# 3020_0323.net
KiCad netlist of a schematic drawn in EasyEDA Pro
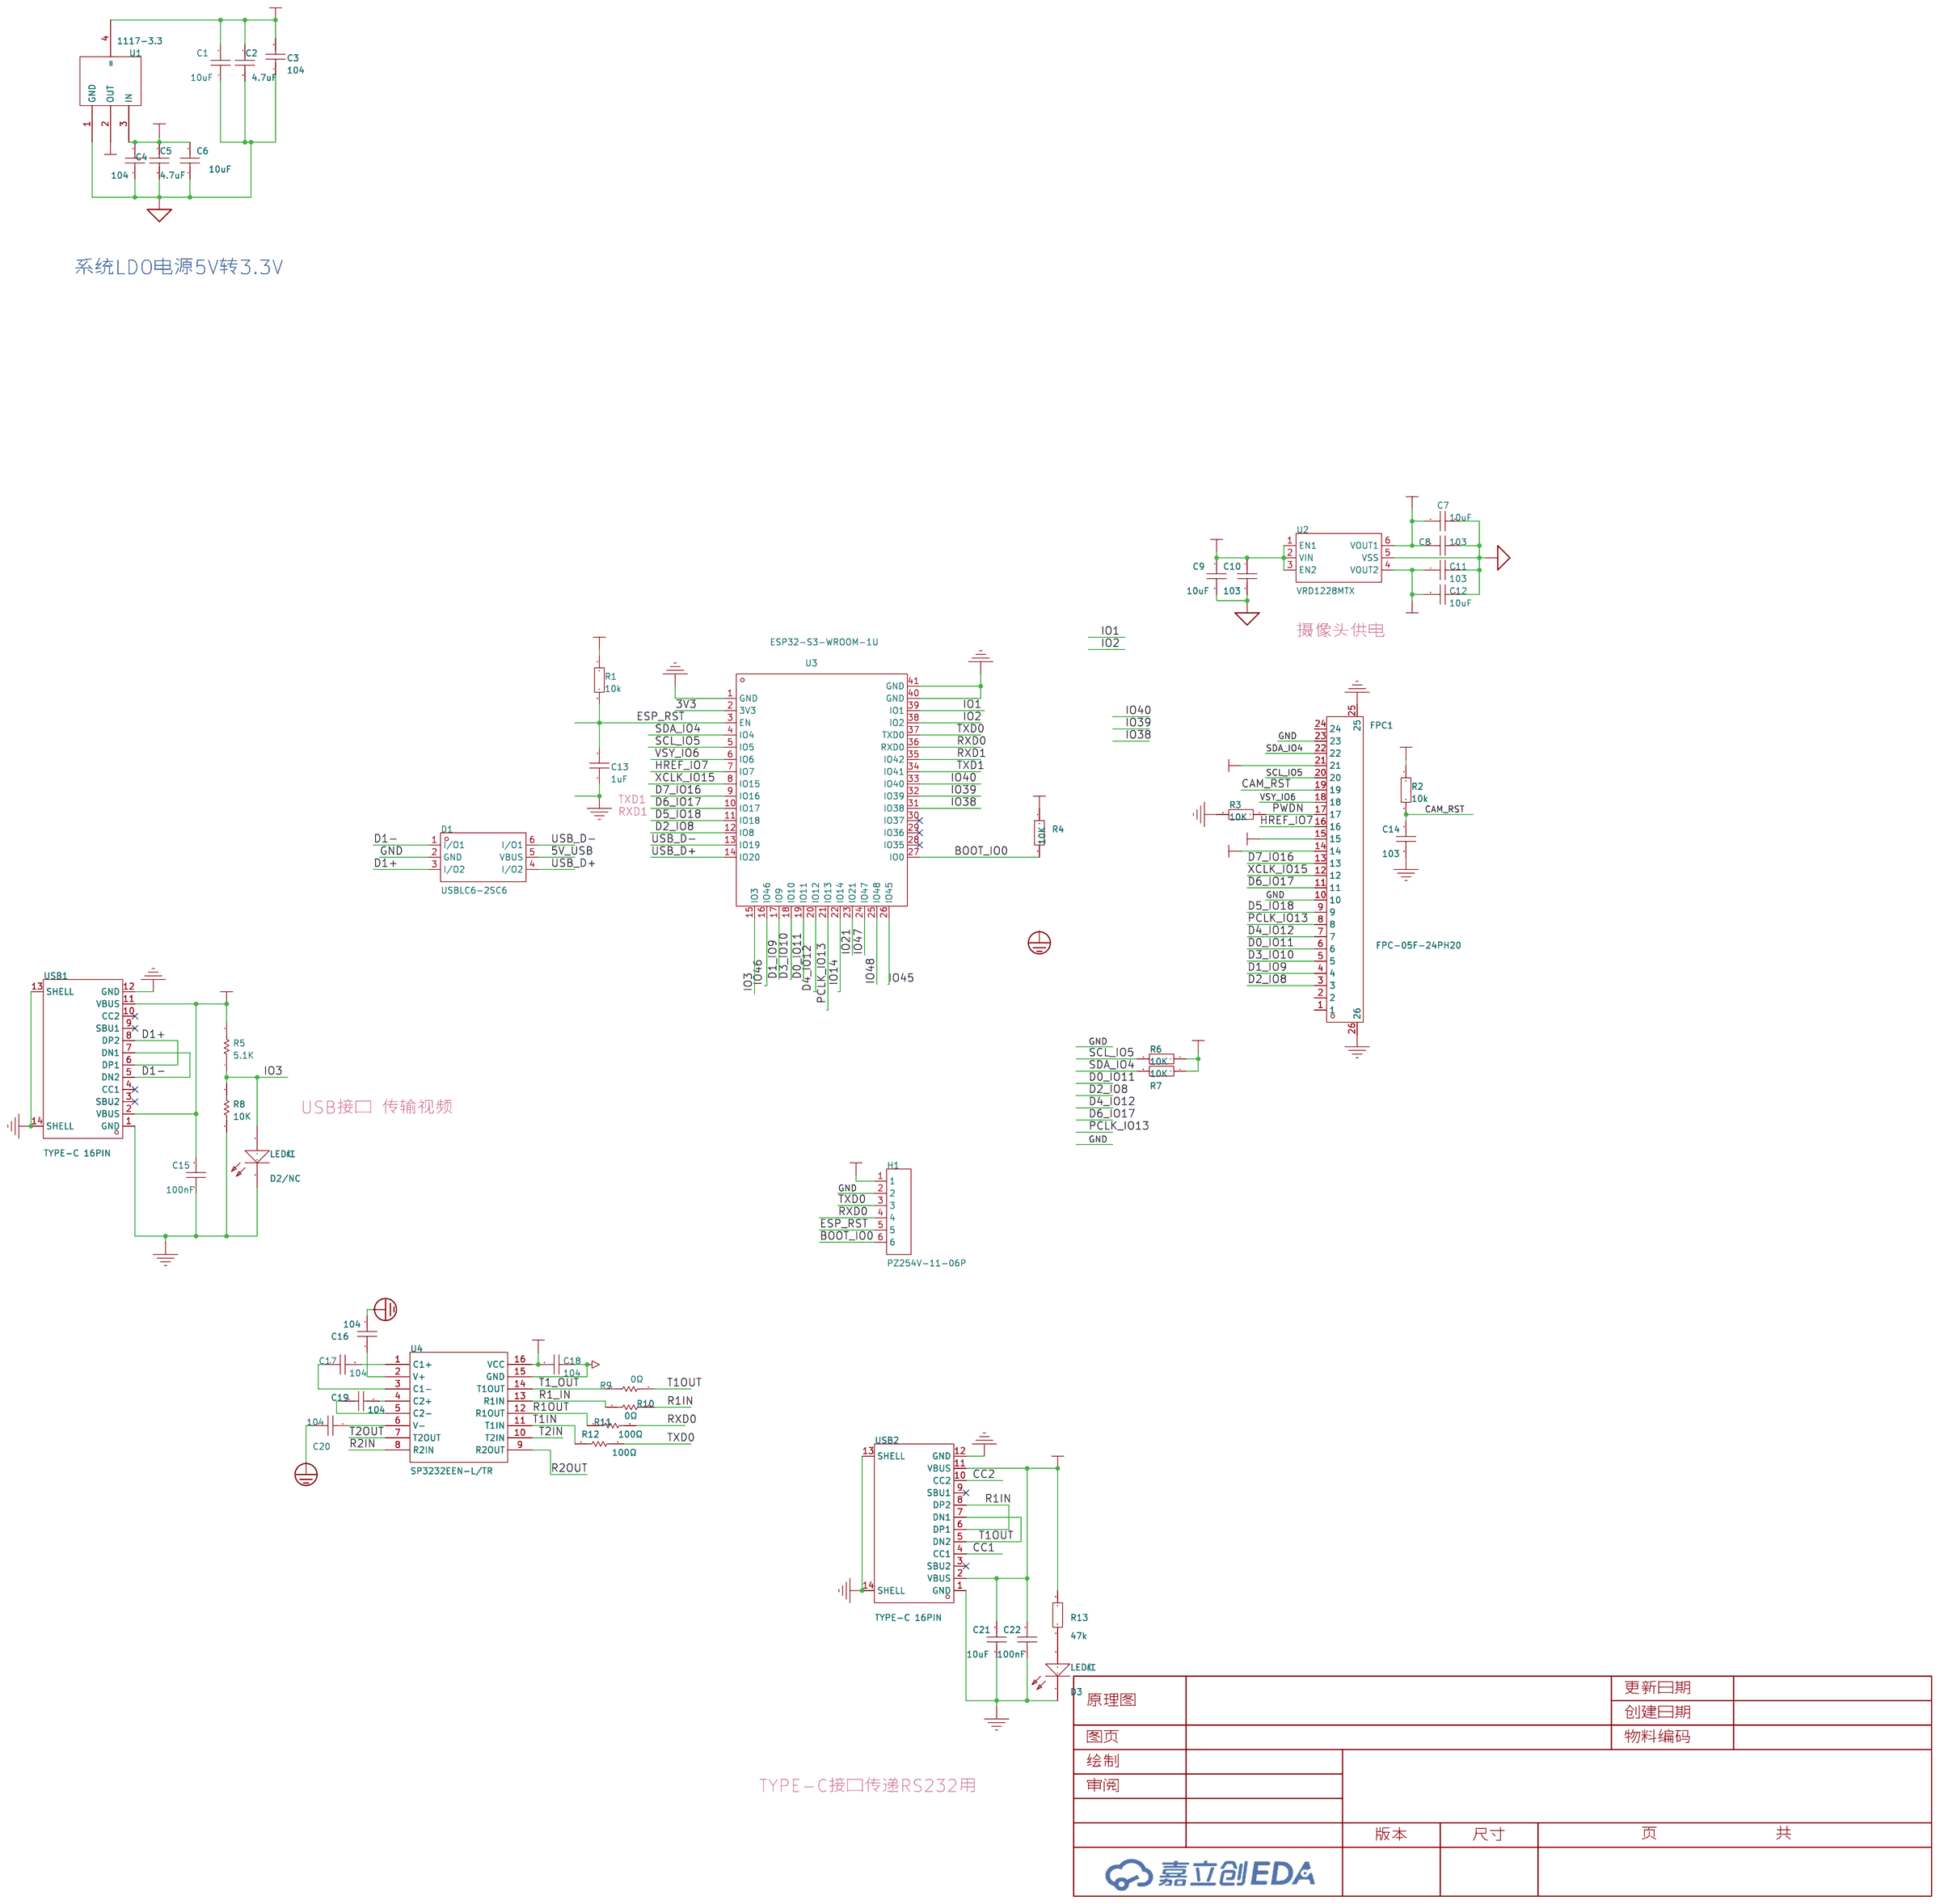
[diagram p0: schematic sheet]

(export (version "E")
  (design (tool "Eeschema 10.0.6"))
  (components
    (comp (ref "C1") (value "10uF") (libsource (lib "easyedapro") (part "CAP")))
    (comp (ref "C2") (value "4.7uF") (libsource (lib "easyedapro") (part "CAP")))
    (comp (ref "C3")
      (value "104")
      (footprint "easyedapro:0603C")
      (description "Capacitor (Semiconductor SIM Model)")
      (libsource (lib "easyedapro") (part "Cap Semi"))
    )
    (comp (ref "C4")
      (value "104")
      (footprint "easyedapro:0603C")
      (description "Capacitor (Semiconductor SIM Model)")
      (libsource (lib "easyedapro") (part "Cap Semi"))
    )
    (comp (ref "C5") (value "4.7uF") (libsource (lib "easyedapro") (part "CAP")))
    (comp (ref "C6") (value "10uF") (libsource (lib "easyedapro") (part "CAP")))
    (comp (ref "C7") (value "10uF") (libsource (lib "easyedapro") (part "CAP")))
    (comp (ref "C8")
      (value "18pF")
      (footprint "easyedapro:0603C")
      (description "Capacitor (Semiconductor SIM Model)")
      (libsource (lib "easyedapro") (part "Cap Semi"))
    )
    (comp (ref "C9") (value "10uF") (libsource (lib "easyedapro") (part "CAP")))
    (comp (ref "C10")
      (value "18pF")
      (footprint "easyedapro:0603C")
      (description "Capacitor (Semiconductor SIM Model)")
      (libsource (lib "easyedapro") (part "Cap Semi"))
    )
    (comp (ref "C11")
      (value "18pF")
      (footprint "easyedapro:0603C")
      (description "Capacitor (Semiconductor SIM Model)")
      (libsource (lib "easyedapro") (part "Cap Semi"))
    )
    (comp (ref "C12") (value "10uF") (libsource (lib "easyedapro") (part "CAP")))
    (comp (ref "C13")
      (value "1uF")
      (footprint "easyedapro:C0603")
      (description "Capacitor")
      (libsource (lib "easyedapro") (part "Cap"))
    )
    (comp (ref "C14")
      (value "18pF")
      (footprint "easyedapro:0603C")
      (description "Capacitor (Semiconductor SIM Model)")
      (libsource (lib "easyedapro") (part "Cap Semi"))
    )
    (comp (ref "C15")
      (value "100nF")
      (footprint "easyedapro:C0603")
      (description "Capacitor")
      (libsource (lib "easyedapro") (part "Cap"))
    )
    (comp (ref "C16")
      (value "104")
      (footprint "easyedapro:0603C")
      (description "Capacitor (Semiconductor SIM Model)")
      (libsource (lib "easyedapro") (part "Cap Semi"))
    )
    (comp (ref "C17")
      (value "104")
      (footprint "easyedapro:0603C")
      (description "Capacitor (Semiconductor SIM Model)")
      (libsource (lib "easyedapro") (part "Cap Semi"))
    )
    (comp (ref "C18")
      (value "104")
      (footprint "easyedapro:0603C")
      (description "Capacitor (Semiconductor SIM Model)")
      (libsource (lib "easyedapro") (part "Cap Semi"))
    )
    (comp (ref "C19")
      (value "104")
      (footprint "easyedapro:0603C")
      (description "Capacitor (Semiconductor SIM Model)")
      (libsource (lib "easyedapro") (part "Cap Semi"))
    )
    (comp (ref "C20")
      (value "104")
      (footprint "easyedapro:0603C")
      (description "Capacitor (Semiconductor SIM Model)")
      (libsource (lib "easyedapro") (part "Cap Semi"))
    )
    (comp (ref "C21") (value "10uF") (libsource (lib "easyedapro") (part "CAP")))
    (comp (ref "C22")
      (value "100nF")
      (footprint "easyedapro:C0603")
      (description "Capacitor")
      (libsource (lib "easyedapro") (part "Cap"))
    )
    (comp (ref "D1")
      (value "USBLC6-2SC6")
      (footprint "easyedapro:SOT-23-6_L2.9-W1.6-P0.95-LS2.8-BL")
      (description "最大钳位电压:15V;击穿电压:6V;")
      (fields (field (name "Manufacturer") "UMW(友台半导体)"))
      (libsource (lib "easyedapro") (part "USBLC6-2SC6_C2687116"))
    )
    (comp (ref "D2/NC")
      (value "LED红")
      (footprint "easyedapro:0603L")
      (description "Typical BLUE SiC LED")
      (libsource (lib "easyedapro") (part "LED3"))
    )
    (comp (ref "D3")
      (value "LED红")
      (footprint "easyedapro:0603L")
      (description "Typical BLUE SiC LED")
      (libsource (lib "easyedapro") (part "LED3"))
    )
    (comp (ref "FPC1")
      (value "FPC-05F-24PH20")
      (footprint "easyedapro:FPC-SMD_24P-P0.50_FPC-05F-24PH20")
      (description "锁定特性:翻盖式;触点类型:卧贴;触点数量:24P;间距:0.5mm;安装方式:下接;工作温度:-25°C~+85°C;")
      (fields (field (name "Manufacturer") "XUNPU(讯普)"))
      (libsource (lib "easyedapro") (part "FPC-05F-24PH20"))
    )
    (comp (ref "H1")
      (value "PZ254V-11-06P")
      (footprint "easyedapro:HDR-TH_6P-P2.54-V-M")
      (fields (field (name "Manufacturer") "XFCN(兴飞)"))
      (libsource (lib "easyedapro") (part "PZ254V-11-06P"))
    )
    (comp (ref "R1")
      (value "10k")
      (footprint "easyedapro:R0603")
      (description "电阻类型:薄膜电阻;阻值:10kΩ;精度:±0.1%;功率:100mW;温度系数:±25ppm/;最大工作电压:75V;工作温度范围:-55~+155;")
      (fields
        (field (name "Manufacturer Part") "RT0603BRD0710KL")
        (field (name "Manufacturer") "YAGEO(----)")
      )
      (libsource (lib "easyedapro") (part "RT0603BRD0710KL"))
    )
    (comp (ref "R2")
      (value "10k")
      (footprint "easyedapro:R0603")
      (description "电阻类型:薄膜电阻;阻值:10kΩ;精度:±0.1%;功率:100mW;温度系数:±25ppm/;最大工作电压:75V;工作温度范围:-55~+155;")
      (fields
        (field (name "Manufacturer Part") "RT0603BRD0710KL")
        (field (name "Manufacturer") "YAGEO(----)")
      )
      (libsource (lib "easyedapro") (part "RT0603BRD0710KL"))
    )
    (comp (ref "R3")
      (value "10K")
      (footprint "easyedapro:R0603")
      (description "电阻类型:薄膜电阻;阻值:10kΩ;精度:±0.1%;功率:100mW;温度系数:±25ppm/;最大工作电压:75V;工作温度范围:-55~+155;")
      (fields
        (field (name "Manufacturer Part") "RT0603BRD0710KL")
        (field (name "Manufacturer") "YAGEO(----)")
      )
      (libsource (lib "easyedapro") (part "RT0603BRD0710KL"))
    )
    (comp (ref "R4")
      (value "10K")
      (footprint "easyedapro:R0603")
      (description "电阻类型:薄膜电阻;阻值:10kΩ;精度:±0.1%;功率:100mW;温度系数:±25ppm/;最大工作电压:75V;工作温度范围:-55~+155;")
      (fields
        (field (name "Manufacturer Part") "RT0603BRD0710KL")
        (field (name "Manufacturer") "YAGEO(----)")
      )
      (libsource (lib "easyedapro") (part "RT0603BRD0710KL"))
    )
    (comp (ref "R5")
      (value "10K")
      (footprint "easyedapro:0603R")
      (description "Resistor")
      (libsource (lib "easyedapro") (part "RES"))
    )
    (comp (ref "R6")
      (value "10K")
      (footprint "easyedapro:R0603")
      (description "电阻类型:薄膜电阻;阻值:10kΩ;精度:±0.1%;功率:100mW;温度系数:±25ppm/;最大工作电压:75V;工作温度范围:-55~+155;")
      (fields
        (field (name "Manufacturer Part") "RT0603BRD0710KL")
        (field (name "Manufacturer") "YAGEO(----)")
      )
      (libsource (lib "easyedapro") (part "RT0603BRD0710KL"))
    )
    (comp (ref "R7")
      (value "10K")
      (footprint "easyedapro:R0603")
      (description "电阻类型:薄膜电阻;阻值:10kΩ;精度:±0.1%;功率:100mW;温度系数:±25ppm/;最大工作电压:75V;工作温度范围:-55~+155;")
      (fields
        (field (name "Manufacturer Part") "RT0603BRD0710KL")
        (field (name "Manufacturer") "YAGEO(----)")
      )
      (libsource (lib "easyedapro") (part "RT0603BRD0710KL"))
    )
    (comp (ref "R8")
      (value "10K")
      (footprint "easyedapro:0603R")
      (description "Resistor")
      (libsource (lib "easyedapro") (part "RES"))
    )
    (comp (ref "R9")
      (value "0Ω")
      (footprint "easyedapro:0603R")
      (description "Resistor")
      (libsource (lib "easyedapro") (part "RES"))
    )
    (comp (ref "R10")
      (value "0Ω")
      (footprint "easyedapro:0603R")
      (description "Resistor")
      (libsource (lib "easyedapro") (part "RES"))
    )
    (comp (ref "R11")
      (value "100Ω")
      (footprint "easyedapro:0603R")
      (description "Resistor")
      (libsource (lib "easyedapro") (part "RES"))
    )
    (comp (ref "R12")
      (value "100Ω")
      (footprint "easyedapro:0603R")
      (description "Resistor")
      (libsource (lib "easyedapro") (part "RES"))
    )
    (comp (ref "R13")
      (value "47k")
      (footprint "easyedapro:R0603")
      (description "电阻类型:薄膜电阻;阻值:10kΩ;精度:±0.1%;功率:100mW;温度系数:±25ppm/;最大工作电压:75V;工作温度范围:-55~+155;")
      (fields
        (field (name "Manufacturer Part") "RT0603BRD0710KL")
        (field (name "Manufacturer") "YAGEO(----)")
      )
      (libsource (lib "easyedapro") (part "RT0603BRD0710KL"))
    )
    (comp (ref "U1")
      (value "1117-3.3")
      (footprint "easyedapro:SOT-223")
      (libsource (lib "easyedapro") (part "LM1117"))
    )
    (comp (ref "U2")
      (value "VRD1228MTX")
      (footprint "easyedapro:SOT-23-6_L2.9-W1.6-P0.95-LS2.8-BL")
      (description "输出类型:-;工作电压:6V;输出电压:1.2V；2.8V;输出电流:-;电源纹波抑制比(PSRR):75dB@(1kHz);输出极性:正极;")
      (fields (field (name "Manufacturer") "AnaSem(安纳森)"))
      (libsource (lib "easyedapro") (part "VRD1228MTX"))
    )
    (comp (ref "U3")
      (value "ESP32-S3-WROOM-1U")
      (footprint "easyedapro:ESP32-S3-WROOM-1U")
      (fields
        (field (name "Manufacturer Part") "ESP32-S3-WROOM-1(N16R2)")
        (field (name "Manufacturer") "ESPRESSIF(----)")
      )
      (libsource (lib "easyedapro") (part "ESP32-S3-WROOM-1(N16R2)"))
    )
    (comp (ref "U4")
      (value "SP3232EEN-L/TR")
      (footprint "easyedapro:SOIC-16_L9.9-W3.9-P1.27-LS6.0-BL")
      (description "类型:收发器;数据速率:235Kbps;")
      (fields (field (name "Manufacturer") "MaxLinear(迈凌)"))
      (libsource (lib "easyedapro") (part "SP3232EEN-L/TR"))
    )
    (comp (ref "USB1")
      (value "TYPE-C 16PIN")
      (footprint "easyedapro:USB-C-SMD_TYPE-C-6PIN-2MD-073")
      (description "连接器类型:Type-C;标准:-;公母:母;端口数量:1;触点数量:16P;安装方式:卧贴;额定电流 - 电源:5A;工作温度范围:-25°C~+85°C;")
      (fields (field (name "Manufacturer") "SHOU HAN(首韩)"))
      (libsource (lib "easyedapro") (part "TYPE-C 16PIN 2MD(073)"))
    )
    (comp (ref "USB2")
      (value "TYPE-C 16PIN")
      (footprint "easyedapro:USB-C-SMD_TYPE-C-6PIN-2MD-073")
      (description "连接器类型:Type-C;标准:-;公母:母;端口数量:1;触点数量:16P;安装方式:卧贴;额定电流 - 电源:5A;工作温度范围:-25°C~+85°C;")
      (fields (field (name "Manufacturer") "SHOU HAN(首韩)"))
      (libsource (lib "easyedapro") (part "TYPE-C 16PIN 2MD(073)"))
    )
  )
  (nets
    (net (code "1") (name "/BOOT_IO0") (class "Default")
      (node (ref "H1") (pin "6") (pinfunction "6_6") (pintype "unspecified"))
      (node (ref "R4") (pin "2") (pinfunction "2_2") (pintype "unspecified"))
      (node (ref "U3") (pin "27") (pinfunction "IO0_27") (pintype "unspecified"))
    )
    (net (code "2") (name "/CAM_RST") (class "Default")
      (node (ref "C14") (pin "1") (pinfunction "1_1") (pintype "unspecified"))
      (node (ref "FPC1") (pin "19") (pinfunction "19_19") (pintype "unspecified"))
      (node (ref "R2") (pin "2") (pinfunction "2_2") (pintype "unspecified"))
    )
    (net (code "3") (name "/CC1") (class "Default")
      (node (ref "USB2") (pin "4") (pinfunction "CC1_4") (pintype "unspecified"))
    )
    (net (code "4") (name "/CC2") (class "Default")
      (node (ref "USB2") (pin "10") (pinfunction "CC2_10") (pintype "unspecified"))
    )
    (net (code "5") (name "/D0_IO11") (class "Default")
      (node (ref "FPC1") (pin "6") (pinfunction "6_6") (pintype "unspecified"))
      (node (ref "U3") (pin "19") (pinfunction "IO11_19") (pintype "unspecified"))
    )
    (net (code "6") (name "/D1+") (class "Default")
      (node (ref "D1") (pin "3") (pinfunction "I/O2_3") (pintype "unspecified"))
      (node (ref "USB1") (pin "6") (pinfunction "DP1_6") (pintype "unspecified"))
      (node (ref "USB1") (pin "8") (pinfunction "DP2_8") (pintype "unspecified"))
    )
    (net (code "7") (name "/D1-") (class "Default")
      (node (ref "D1") (pin "1") (pinfunction "I/O1_1") (pintype "unspecified"))
      (node (ref "USB1") (pin "5") (pinfunction "DN2_5") (pintype "unspecified"))
      (node (ref "USB1") (pin "7") (pinfunction "DN1_7") (pintype "unspecified"))
    )
    (net (code "8") (name "/D1_IO9") (class "Default")
      (node (ref "FPC1") (pin "4") (pinfunction "4_4") (pintype "unspecified"))
      (node (ref "U3") (pin "17") (pinfunction "IO9_17") (pintype "unspecified"))
    )
    (net (code "9") (name "/D2_IO8") (class "Default")
      (node (ref "FPC1") (pin "3") (pinfunction "3_3") (pintype "unspecified"))
      (node (ref "U3") (pin "12") (pinfunction "IO8_12") (pintype "unspecified"))
    )
    (net (code "10") (name "/D3_IO10") (class "Default")
      (node (ref "FPC1") (pin "5") (pinfunction "5_5") (pintype "unspecified"))
      (node (ref "U3") (pin "18") (pinfunction "IO10_18") (pintype "unspecified"))
    )
    (net (code "11") (name "/D4_IO12") (class "Default")
      (node (ref "FPC1") (pin "7") (pinfunction "7_7") (pintype "unspecified"))
      (node (ref "U3") (pin "20") (pinfunction "IO12_20") (pintype "unspecified"))
    )
    (net (code "12") (name "/D5_IO18") (class "Default")
      (node (ref "FPC1") (pin "9") (pinfunction "9_9") (pintype "unspecified"))
      (node (ref "U3") (pin "11") (pinfunction "IO18_11") (pintype "unspecified"))
    )
    (net (code "13") (name "/D6_IO17") (class "Default")
      (node (ref "FPC1") (pin "11") (pinfunction "11_11") (pintype "unspecified"))
      (node (ref "U3") (pin "10") (pinfunction "IO17_10") (pintype "unspecified"))
    )
    (net (code "14") (name "/D7_IO16") (class "Default")
      (node (ref "FPC1") (pin "13") (pinfunction "13_13") (pintype "unspecified"))
      (node (ref "U3") (pin "9") (pinfunction "IO16_9") (pintype "unspecified"))
    )
    (net (code "15") (name "/ESP_RST") (class "Default")
      (node (ref "C13") (pin "2") (pinfunction "2_2") (pintype "unspecified"))
      (node (ref "H1") (pin "5") (pinfunction "5_5") (pintype "unspecified"))
      (node (ref "R1") (pin "2") (pinfunction "2_2") (pintype "unspecified"))
      (node (ref "U3") (pin "3") (pinfunction "EN_3") (pintype "unspecified"))
    )
    (net (code "16") (name "/HREF_IO7") (class "Default")
      (node (ref "FPC1") (pin "16") (pinfunction "16_16") (pintype "unspecified"))
      (node (ref "U3") (pin "7") (pinfunction "IO7_7") (pintype "unspecified"))
    )
    (net (code "17") (name "/IO1") (class "Default")
      (node (ref "U3") (pin "39") (pinfunction "IO1_39") (pintype "unspecified"))
    )
    (net (code "18") (name "/IO2") (class "Default")
      (node (ref "U3") (pin "38") (pinfunction "IO2_38") (pintype "unspecified"))
    )
    (net (code "19") (name "/IO3") (class "Default")
      (node (ref "D2/NC") (pin "1") (pinfunction "A_1") (pintype "unspecified"))
      (node (ref "R5") (pin "1") (pinfunction "1_1") (pintype "unspecified"))
      (node (ref "R8") (pin "2") (pinfunction "2_2") (pintype "unspecified"))
      (node (ref "U3") (pin "15") (pinfunction "IO3_15") (pintype "unspecified"))
    )
    (net (code "20") (name "/IO14") (class "Default")
      (node (ref "U3") (pin "22") (pinfunction "IO14_22") (pintype "unspecified"))
    )
    (net (code "21") (name "/IO21") (class "Default")
      (node (ref "U3") (pin "23") (pinfunction "IO21_23") (pintype "unspecified"))
    )
    (net (code "22") (name "/IO38") (class "Default")
      (node (ref "U3") (pin "31") (pinfunction "IO38_31") (pintype "unspecified"))
    )
    (net (code "23") (name "/IO39") (class "Default")
      (node (ref "U3") (pin "32") (pinfunction "IO39_32") (pintype "unspecified"))
    )
    (net (code "24") (name "/IO40") (class "Default")
      (node (ref "U3") (pin "33") (pinfunction "IO40_33") (pintype "unspecified"))
    )
    (net (code "25") (name "/IO45") (class "Default")
      (node (ref "U3") (pin "26") (pinfunction "IO45_26") (pintype "unspecified"))
    )
    (net (code "26") (name "/IO46") (class "Default")
      (node (ref "U3") (pin "16") (pinfunction "IO46_16") (pintype "unspecified"))
    )
    (net (code "27") (name "/IO47") (class "Default")
      (node (ref "U3") (pin "24") (pinfunction "IO47_24") (pintype "unspecified"))
    )
    (net (code "28") (name "/IO48") (class "Default")
      (node (ref "U3") (pin "25") (pinfunction "IO48_25") (pintype "unspecified"))
    )
    (net (code "29") (name "/PCLK_IO13") (class "Default")
      (node (ref "FPC1") (pin "8") (pinfunction "8_8") (pintype "unspecified"))
      (node (ref "U3") (pin "21") (pinfunction "IO13_21") (pintype "unspecified"))
    )
    (net (code "30") (name "/PWDN") (class "Default")
      (node (ref "FPC1") (pin "17") (pinfunction "17_17") (pintype "unspecified"))
      (node (ref "R3") (pin "1") (pinfunction "1_1") (pintype "unspecified"))
    )
    (net (code "31") (name "/R1IN") (class "Default")
      (node (ref "R10") (pin "2") (pinfunction "2_2") (pintype "unspecified"))
      (node (ref "USB2") (pin "6") (pinfunction "DP1_6") (pintype "unspecified"))
      (node (ref "USB2") (pin "8") (pinfunction "DP2_8") (pintype "unspecified"))
    )
    (net (code "32") (name "/R1OUT") (class "Default")
      (node (ref "R11") (pin "1") (pinfunction "1_1") (pintype "unspecified"))
      (node (ref "U4") (pin "12") (pinfunction "R1OUT_12") (pintype "unspecified"))
    )
    (net (code "33") (name "/R1_IN") (class "Default")
      (node (ref "R10") (pin "1") (pinfunction "1_1") (pintype "unspecified"))
      (node (ref "U4") (pin "13") (pinfunction "R1IN_13") (pintype "unspecified"))
    )
    (net (code "34") (name "/R2IN") (class "Default")
      (node (ref "U4") (pin "8") (pinfunction "R2IN_8") (pintype "unspecified"))
    )
    (net (code "35") (name "/R2OUT") (class "Default")
      (node (ref "U4") (pin "9") (pinfunction "R2OUT_9") (pintype "unspecified"))
    )
    (net (code "36") (name "/RXD0") (class "Default")
      (node (ref "H1") (pin "4") (pinfunction "4_4") (pintype "unspecified"))
      (node (ref "R11") (pin "2") (pinfunction "2_2") (pintype "unspecified"))
      (node (ref "U3") (pin "36") (pinfunction "RXD0_36") (pintype "unspecified"))
    )
    (net (code "37") (name "/RXD1") (class "Default")
      (node (ref "U3") (pin "35") (pinfunction "IO42_35") (pintype "unspecified"))
    )
    (net (code "38") (name "/SCL_IO5") (class "Default")
      (node (ref "FPC1") (pin "20") (pinfunction "20_20") (pintype "unspecified"))
      (node (ref "R6") (pin "2") (pinfunction "2_2") (pintype "unspecified"))
      (node (ref "U3") (pin "5") (pinfunction "IO5_5") (pintype "unspecified"))
    )
    (net (code "39") (name "/SDA_IO4") (class "Default")
      (node (ref "FPC1") (pin "22") (pinfunction "22_22") (pintype "unspecified"))
      (node (ref "R7") (pin "2") (pinfunction "2_2") (pintype "unspecified"))
      (node (ref "U3") (pin "4") (pinfunction "IO4_4") (pintype "unspecified"))
    )
    (net (code "40") (name "/T1IN") (class "Default")
      (node (ref "R12") (pin "1") (pinfunction "1_1") (pintype "unspecified"))
      (node (ref "U4") (pin "11") (pinfunction "T1IN_11") (pintype "unspecified"))
    )
    (net (code "41") (name "/T1OUT") (class "Default")
      (node (ref "R9") (pin "2") (pinfunction "2_2") (pintype "unspecified"))
      (node (ref "USB2") (pin "5") (pinfunction "DN2_5") (pintype "unspecified"))
      (node (ref "USB2") (pin "7") (pinfunction "DN1_7") (pintype "unspecified"))
    )
    (net (code "42") (name "/T1_OUT") (class "Default")
      (node (ref "R9") (pin "1") (pinfunction "1_1") (pintype "unspecified"))
      (node (ref "U4") (pin "14") (pinfunction "T1OUT_14") (pintype "unspecified"))
    )
    (net (code "43") (name "/T2IN") (class "Default")
      (node (ref "U4") (pin "10") (pinfunction "T2IN_10") (pintype "unspecified"))
    )
    (net (code "44") (name "/T2OUT") (class "Default")
      (node (ref "U4") (pin "7") (pinfunction "T2OUT_7") (pintype "unspecified"))
    )
    (net (code "45") (name "/TXD0") (class "Default")
      (node (ref "H1") (pin "3") (pinfunction "3_3") (pintype "unspecified"))
      (node (ref "R12") (pin "2") (pinfunction "2_2") (pintype "unspecified"))
      (node (ref "U3") (pin "37") (pinfunction "TXD0_37") (pintype "unspecified"))
    )
    (net (code "46") (name "/TXD1") (class "Default")
      (node (ref "U3") (pin "34") (pinfunction "IO41_34") (pintype "unspecified"))
    )
    (net (code "47") (name "/USB_D+") (class "Default")
      (node (ref "D1") (pin "4") (pinfunction "I/O2_4") (pintype "unspecified"))
      (node (ref "U3") (pin "14") (pinfunction "IO20_14") (pintype "unspecified"))
    )
    (net (code "48") (name "/USB_D-") (class "Default")
      (node (ref "D1") (pin "6") (pinfunction "I/O1_6") (pintype "unspecified"))
      (node (ref "U3") (pin "13") (pinfunction "IO19_13") (pintype "unspecified"))
    )
    (net (code "49") (name "/VSY_IO6") (class "Default")
      (node (ref "FPC1") (pin "18") (pinfunction "18_18") (pintype "unspecified"))
      (node (ref "U3") (pin "6") (pinfunction "IO6_6") (pintype "unspecified"))
    )
    (net (code "50") (name "/XCLK_IO15") (class "Default")
      (node (ref "FPC1") (pin "12") (pinfunction "12_12") (pintype "unspecified"))
      (node (ref "U3") (pin "8") (pinfunction "IO15_8") (pintype "unspecified"))
    )
    (net (code "51") (name "1.2V") (class "Default")
      (node (ref "C7") (pin "1") (pinfunction "1_1") (pintype "input"))
      (node (ref "C8") (pin "1") (pinfunction "1_1") (pintype "unspecified"))
      (node (ref "FPC1") (pin "15") (pinfunction "15_15") (pintype "unspecified"))
      (node (ref "U2") (pin "6") (pinfunction "VOUT1_6") (pintype "unspecified"))
    )
    (net (code "52") (name "2.8V") (class "Default")
      (node (ref "C11") (pin "1") (pinfunction "1_1") (pintype "unspecified"))
      (node (ref "C12") (pin "1") (pinfunction "1_1") (pintype "input"))
      (node (ref "FPC1") (pin "14") (pinfunction "14_14") (pintype "unspecified"))
      (node (ref "FPC1") (pin "21") (pinfunction "21_21") (pintype "unspecified"))
      (node (ref "U2") (pin "4") (pinfunction "VOUT2_4") (pintype "unspecified"))
    )
    (net (code "53") (name "3V3") (class "Default")
      (node (ref "C1") (pin "2") (pinfunction "2_2") (pintype "input"))
      (node (ref "C2") (pin "1") (pinfunction "1_1") (pintype "input"))
      (node (ref "C3") (pin "2") (pinfunction "2_2") (pintype "unspecified"))
      (node (ref "R1") (pin "1") (pinfunction "1_1") (pintype "unspecified"))
      (node (ref "R2") (pin "1") (pinfunction "1_1") (pintype "unspecified"))
      (node (ref "R4") (pin "1") (pinfunction "1_1") (pintype "unspecified"))
      (node (ref "R6") (pin "1") (pinfunction "1_1") (pintype "unspecified"))
      (node (ref "R7") (pin "1") (pinfunction "1_1") (pintype "unspecified"))
      (node (ref "U1") (pin "2") (pinfunction "OUT_2") (pintype "unspecified"))
      (node (ref "U1") (pin "4") (pinfunction "=_4") (pintype "unspecified"))
      (node (ref "U3") (pin "2") (pinfunction "3V3_2") (pintype "unspecified"))
    )
    (net (code "54") (name "5V_USB") (class "Default")
      (node (ref "C15") (pin "2") (pinfunction "2_2") (pintype "unspecified"))
      (node (ref "D1") (pin "5") (pinfunction "VBUS_5") (pintype "unspecified"))
      (node (ref "R5") (pin "2") (pinfunction "2_2") (pintype "unspecified"))
      (node (ref "USB1") (pin "11") (pinfunction "VBUS_11") (pintype "unspecified"))
      (node (ref "USB1") (pin "2") (pinfunction "VBUS_2") (pintype "unspecified"))
    )
    (net (code "55") (name "5V_VCC") (class "Default")
      (node (ref "C10") (pin "1") (pinfunction "1_1") (pintype "unspecified"))
      (node (ref "C18") (pin "2") (pinfunction "2_2") (pintype "unspecified"))
      (node (ref "C21") (pin "2") (pinfunction "2_2") (pintype "input"))
      (node (ref "C22") (pin "2") (pinfunction "2_2") (pintype "unspecified"))
      (node (ref "C4") (pin "2") (pinfunction "2_2") (pintype "unspecified"))
      (node (ref "C5") (pin "1") (pinfunction "1_1") (pintype "input"))
      (node (ref "C6") (pin "2") (pinfunction "2_2") (pintype "input"))
      (node (ref "C9") (pin "1") (pinfunction "1_1") (pintype "input"))
      (node (ref "H1") (pin "1") (pinfunction "1_1") (pintype "unspecified"))
      (node (ref "R13") (pin "2") (pinfunction "2_2") (pintype "unspecified"))
      (node (ref "U1") (pin "3") (pinfunction "IN_3") (pintype "unspecified"))
      (node (ref "U2") (pin "1") (pinfunction "EN1_1") (pintype "unspecified"))
      (node (ref "U2") (pin "2") (pinfunction "VIN_2") (pintype "unspecified"))
      (node (ref "U2") (pin "3") (pinfunction "EN2_3") (pintype "unspecified"))
      (node (ref "U4") (pin "16") (pinfunction "VCC_16") (pintype "unspecified"))
      (node (ref "USB2") (pin "11") (pinfunction "VBUS_11") (pintype "unspecified"))
      (node (ref "USB2") (pin "2") (pinfunction "VBUS_2") (pintype "unspecified"))
    )
    (net (code "56") (name "GND") (class "Default")
      (node (ref "C1") (pin "1") (pinfunction "1_1") (pintype "input"))
      (node (ref "C10") (pin "2") (pinfunction "2_2") (pintype "unspecified"))
      (node (ref "C11") (pin "2") (pinfunction "2_2") (pintype "unspecified"))
      (node (ref "C12") (pin "2") (pinfunction "2_2") (pintype "input"))
      (node (ref "C13") (pin "1") (pinfunction "1_1") (pintype "unspecified"))
      (node (ref "C14") (pin "2") (pinfunction "2_2") (pintype "unspecified"))
      (node (ref "C15") (pin "1") (pinfunction "1_1") (pintype "unspecified"))
      (node (ref "C16") (pin "1") (pinfunction "1_1") (pintype "unspecified"))
      (node (ref "C18") (pin "1") (pinfunction "1_1") (pintype "unspecified"))
      (node (ref "C2") (pin "2") (pinfunction "2_2") (pintype "input"))
      (node (ref "C20") (pin "2") (pinfunction "2_2") (pintype "unspecified"))
      (node (ref "C21") (pin "1") (pinfunction "1_1") (pintype "input"))
      (node (ref "C22") (pin "1") (pinfunction "1_1") (pintype "unspecified"))
      (node (ref "C3") (pin "1") (pinfunction "1_1") (pintype "unspecified"))
      (node (ref "C4") (pin "1") (pinfunction "1_1") (pintype "unspecified"))
      (node (ref "C5") (pin "2") (pinfunction "2_2") (pintype "input"))
      (node (ref "C6") (pin "1") (pinfunction "1_1") (pintype "input"))
      (node (ref "C7") (pin "2") (pinfunction "2_2") (pintype "input"))
      (node (ref "C8") (pin "2") (pinfunction "2_2") (pintype "unspecified"))
      (node (ref "C9") (pin "2") (pinfunction "2_2") (pintype "input"))
      (node (ref "D1") (pin "2") (pinfunction "GND_2") (pintype "unspecified"))
      (node (ref "D2/NC") (pin "2") (pinfunction "K_2") (pintype "unspecified"))
      (node (ref "D3") (pin "2") (pinfunction "K_2") (pintype "unspecified"))
      (node (ref "FPC1") (pin "10") (pinfunction "10_10") (pintype "unspecified"))
      (node (ref "FPC1") (pin "23") (pinfunction "23_23") (pintype "unspecified"))
      (node (ref "FPC1") (pin "25") (pinfunction "25_25") (pintype "unspecified"))
      (node (ref "FPC1") (pin "26") (pinfunction "26_26") (pintype "unspecified"))
      (node (ref "H1") (pin "2") (pinfunction "2_2") (pintype "unspecified"))
      (node (ref "R3") (pin "2") (pinfunction "2_2") (pintype "unspecified"))
      (node (ref "R8") (pin "1") (pinfunction "1_1") (pintype "unspecified"))
      (node (ref "U1") (pin "1") (pinfunction "GND_1") (pintype "unspecified"))
      (node (ref "U2") (pin "5") (pinfunction "VSS_5") (pintype "unspecified"))
      (node (ref "U3") (pin "1") (pinfunction "GND_1") (pintype "unspecified"))
      (node (ref "U3") (pin "40") (pinfunction "GND_40") (pintype "unspecified"))
      (node (ref "U3") (pin "41") (pinfunction "GND_41") (pintype "unspecified"))
      (node (ref "U4") (pin "15") (pinfunction "GND_15") (pintype "unspecified"))
      (node (ref "USB1") (pin "1") (pinfunction "GND_1") (pintype "unspecified"))
      (node (ref "USB1") (pin "12") (pinfunction "GND_12") (pintype "unspecified"))
      (node (ref "USB1") (pin "13") (pinfunction "SHELL_13") (pintype "unspecified"))
      (node (ref "USB1") (pin "14") (pinfunction "SHELL_14") (pintype "unspecified"))
      (node (ref "USB2") (pin "1") (pinfunction "GND_1") (pintype "unspecified"))
      (node (ref "USB2") (pin "12") (pinfunction "GND_12") (pintype "unspecified"))
      (node (ref "USB2") (pin "13") (pinfunction "SHELL_13") (pintype "unspecified"))
      (node (ref "USB2") (pin "14") (pinfunction "SHELL_14") (pintype "unspecified"))
    )
    (net (code "57") (name "Net-(D3-A)") (class "Default")
      (node (ref "D3") (pin "1") (pinfunction "A_1") (pintype "unspecified"))
      (node (ref "R13") (pin "1") (pinfunction "1_1") (pintype "unspecified"))
    )
    (net (code "58") (name "Net-(U4-C1+)") (class "Default")
      (node (ref "C17") (pin "2") (pinfunction "2_2") (pintype "unspecified"))
      (node (ref "U4") (pin "1") (pinfunction "C1+_1") (pintype "unspecified"))
    )
    (net (code "59") (name "Net-(U4-C1-)") (class "Default")
      (node (ref "C17") (pin "1") (pinfunction "1_1") (pintype "unspecified"))
      (node (ref "U4") (pin "3") (pinfunction "C1-_3") (pintype "unspecified"))
    )
    (net (code "60") (name "Net-(U4-C2+)") (class "Default")
      (node (ref "C19") (pin "2") (pinfunction "2_2") (pintype "unspecified"))
      (node (ref "U4") (pin "4") (pinfunction "C2+_4") (pintype "unspecified"))
    )
    (net (code "61") (name "Net-(U4-C2-)") (class "Default")
      (node (ref "C19") (pin "1") (pinfunction "1_1") (pintype "unspecified"))
      (node (ref "U4") (pin "5") (pinfunction "C2-_5") (pintype "unspecified"))
    )
    (net (code "62") (name "Net-(U4-V+)") (class "Default")
      (node (ref "C16") (pin "2") (pinfunction "2_2") (pintype "unspecified"))
      (node (ref "U4") (pin "2") (pinfunction "V+_2") (pintype "unspecified"))
    )
    (net (code "63") (name "Net-(U4-V-)") (class "Default")
      (node (ref "C20") (pin "1") (pinfunction "1_1") (pintype "unspecified"))
      (node (ref "U4") (pin "6") (pinfunction "V-_6") (pintype "unspecified"))
    )
    (net (code "64") (name "unconnected-(FPC1-Pad1)") (class "Default")
      (node (ref "FPC1") (pin "1") (pinfunction "1_1") (pintype "unspecified"))
    )
    (net (code "65") (name "unconnected-(FPC1-Pad2)") (class "Default")
      (node (ref "FPC1") (pin "2") (pinfunction "2_2") (pintype "unspecified"))
    )
    (net (code "66") (name "unconnected-(FPC1-Pad24)") (class "Default")
      (node (ref "FPC1") (pin "24") (pinfunction "24_24") (pintype "unspecified"))
    )
    (net (code "67") (name "unconnected-(U3-IO35-Pad28)") (class "Default")
      (node (ref "U3") (pin "28") (pinfunction "IO35_28") (pintype "unspecified+no_connect"))
    )
    (net (code "68") (name "unconnected-(U3-IO36-Pad29)") (class "Default")
      (node (ref "U3") (pin "29") (pinfunction "IO36_29") (pintype "unspecified+no_connect"))
    )
    (net (code "69") (name "unconnected-(U3-IO37-Pad30)") (class "Default")
      (node (ref "U3") (pin "30") (pinfunction "IO37_30") (pintype "unspecified+no_connect"))
    )
    (net (code "70") (name "unconnected-(USB1-CC1-Pad4)") (class "Default")
      (node (ref "USB1") (pin "4") (pinfunction "CC1_4") (pintype "unspecified+no_connect"))
    )
    (net (code "71") (name "unconnected-(USB1-CC2-Pad10)") (class "Default")
      (node (ref "USB1") (pin "10") (pinfunction "CC2_10") (pintype "unspecified+no_connect"))
    )
    (net (code "72") (name "unconnected-(USB1-SBU1-Pad9)") (class "Default")
      (node (ref "USB1") (pin "9") (pinfunction "SBU1_9") (pintype "unspecified+no_connect"))
    )
    (net (code "73") (name "unconnected-(USB1-SBU2-Pad3)") (class "Default")
      (node (ref "USB1") (pin "3") (pinfunction "SBU2_3") (pintype "unspecified+no_connect"))
    )
    (net (code "74") (name "unconnected-(USB2-SBU1-Pad9)") (class "Default")
      (node (ref "USB2") (pin "9") (pinfunction "SBU1_9") (pintype "unspecified+no_connect"))
    )
    (net (code "75") (name "unconnected-(USB2-SBU2-Pad3)") (class "Default")
      (node (ref "USB2") (pin "3") (pinfunction "SBU2_3") (pintype "unspecified+no_connect"))
    )
  )
)
